# RcMPPT-Debug.net
KiCad netlist of a schematic drawn in Altium Designer
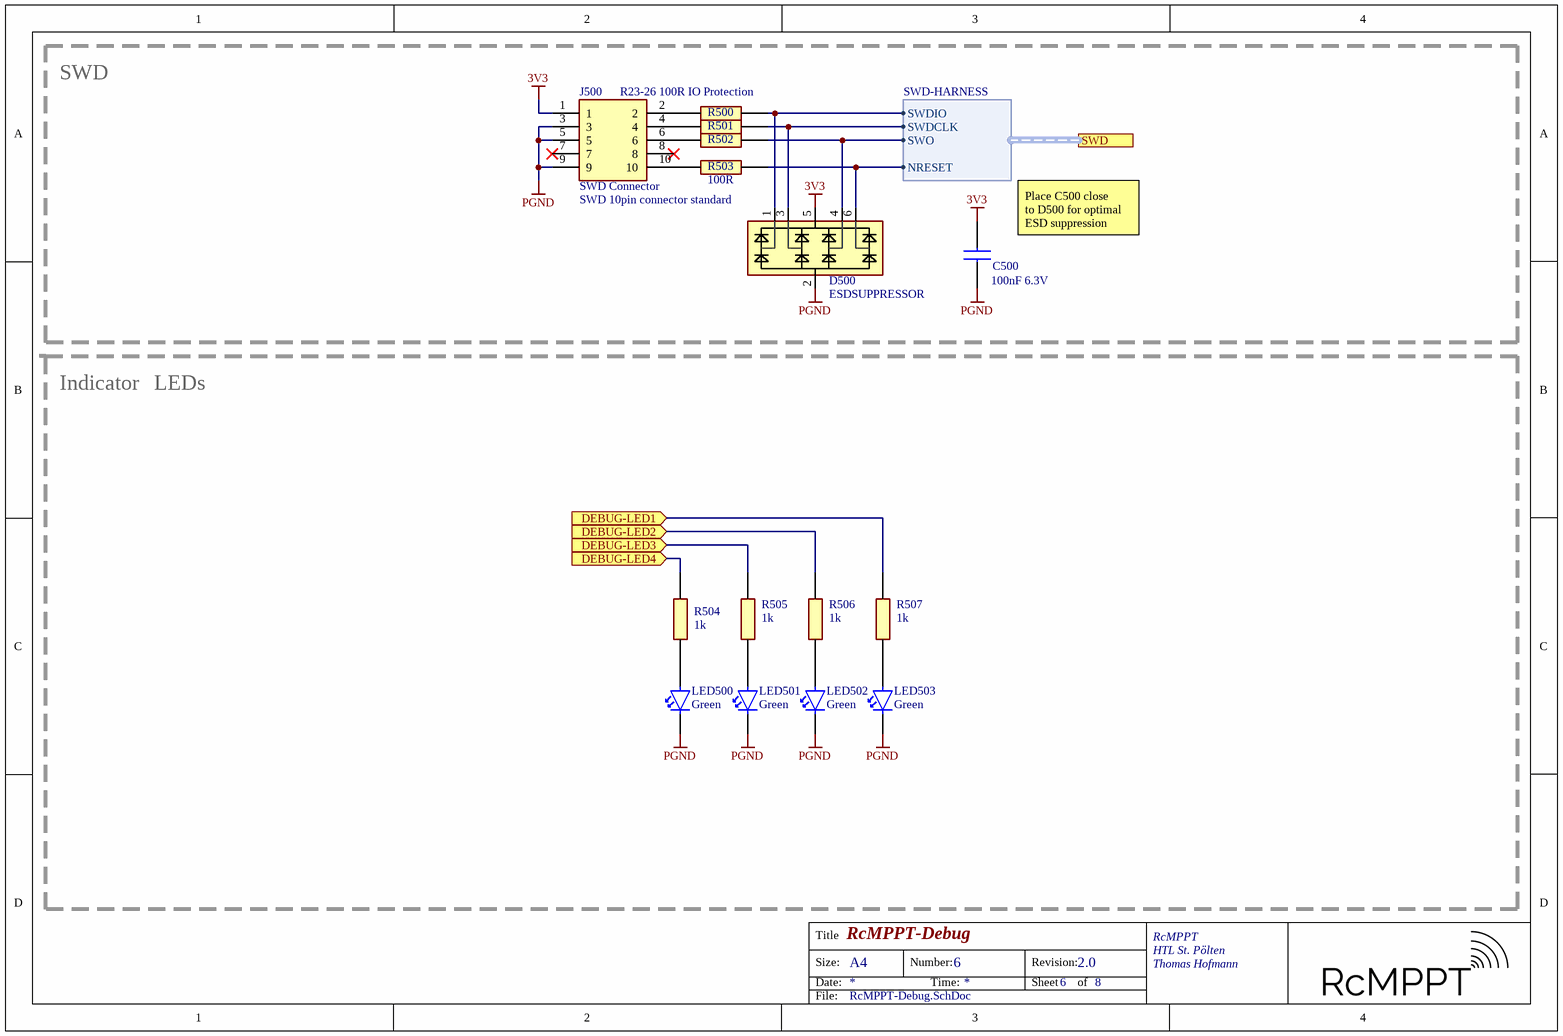
[diagram p0: RcMPPT-Debug.SchDoc]

(export (version "E")
  (design (tool "Eeschema 10.0.6"))
  (components
    (comp (ref "C500")
      (value "100nF 6.3V")
      (footprint "CAPC1608X97N")
      (description "Capacitor")
      (libsource (lib "RcMPPTLib") (part "C0603"))
    )
    (comp (ref "D500")
      (value "ESDSUPPRESSOR")
      (footprint "SOT23-6")
      (description "TVS Diode Array")
      (libsource (lib "RcMPPTLib") (part "ESDSUPPRESSOR"))
    )
    (comp (ref "J500")
      (value "SWD Connector")
      (footprint "HUSSP10W40P127_2X5_635X340X420P")
      (description "Connector")
      (fields
        (field (name "MANUFACTURER_PART_NUMBER") "M50-3600542R")
        (field (name "MOUSER PART NUMBER") "855-M50-3600542R")
      )
      (libsource (lib "RcMPPTLib") (part "M50-3600542R"))
    )
    (comp (ref "LED500")
      (value "Green")
      (footprint "CHIPLED_0603")
      (description "LED")
      (libsource (lib "RcMPPTLib") (part "CHIPLED0603"))
    )
    (comp (ref "LED501")
      (value "Green")
      (footprint "CHIPLED_0603")
      (description "LED")
      (libsource (lib "RcMPPTLib") (part "CHIPLED0603"))
    )
    (comp (ref "LED502")
      (value "Green")
      (footprint "CHIPLED_0603")
      (description "LED")
      (libsource (lib "RcMPPTLib") (part "CHIPLED0603"))
    )
    (comp (ref "LED503")
      (value "Green")
      (footprint "CHIPLED_0603")
      (description "LED")
      (libsource (lib "RcMPPTLib") (part "CHIPLED0603"))
    )
    (comp (ref "R500")
      (value "100R")
      (footprint "RESC1005X40N")
      (description "Resistor")
      (libsource (lib "RcMPPTLib") (part "R0402"))
    )
    (comp (ref "R501")
      (value "100R")
      (footprint "RESC1005X40N")
      (description "Resistor")
      (libsource (lib "RcMPPTLib") (part "R0402"))
    )
    (comp (ref "R502")
      (value "100R")
      (footprint "RESC1005X40N")
      (description "Resistor")
      (libsource (lib "RcMPPTLib") (part "R0402"))
    )
    (comp (ref "R503")
      (value "100R")
      (footprint "RESC1005X40N")
      (description "Resistor")
      (libsource (lib "RcMPPTLib") (part "R0402"))
    )
    (comp (ref "R504")
      (value "1k")
      (footprint "RESC1608X50N")
      (description "Resistor")
      (libsource (lib "RcMPPTLib") (part "R0603"))
    )
    (comp (ref "R505")
      (value "1k")
      (footprint "RESC1608X50N")
      (description "Resistor")
      (libsource (lib "RcMPPTLib") (part "R0603"))
    )
    (comp (ref "R506")
      (value "1k")
      (footprint "RESC1608X50N")
      (description "Resistor")
      (libsource (lib "RcMPPTLib") (part "R0603"))
    )
    (comp (ref "R507")
      (value "1k")
      (footprint "RESC1608X50N")
      (description "Resistor")
      (libsource (lib "RcMPPTLib") (part "R0603"))
    )
  )
  (nets
    (net (code "2") (name "/DEBUG-LED1") (class "Default")
      (node (ref "R507") (pin "1") (pinfunction "1_1") (pintype "passive"))
    )
    (net (code "3") (name "/DEBUG-LED2") (class "Default")
      (node (ref "R506") (pin "1") (pinfunction "1_1") (pintype "passive"))
    )
    (net (code "4") (name "/DEBUG-LED3") (class "Default")
      (node (ref "R505") (pin "1") (pinfunction "1_1") (pintype "passive"))
    )
    (net (code "5") (name "/DEBUG-LED4") (class "Default")
      (node (ref "R504") (pin "1") (pinfunction "1_1") (pintype "passive"))
    )
    (net (code "7") (name "3V3") (class "Default")
      (node (ref "C500") (pin "2") (pinfunction "2_2") (pintype "passive"))
      (node (ref "D500") (pin "5") (pinfunction "VDD_5") (pintype "passive"))
      (node (ref "J500") (pin "1") (pinfunction "1_1") (pintype "passive"))
    )
    (net (code "8") (name "Net-(D500-CH1)") (class "Default")
      (node (ref "D500") (pin "1") (pinfunction "CH1_1") (pintype "passive"))
      (node (ref "R500") (pin "2") (pinfunction "2_2") (pintype "passive"))
    )
    (net (code "9") (name "Net-(D500-CH2)") (class "Default")
      (node (ref "D500") (pin "3") (pinfunction "CH2_3") (pintype "passive"))
      (node (ref "R501") (pin "2") (pinfunction "2_2") (pintype "passive"))
    )
    (net (code "10") (name "Net-(D500-CH3)") (class "Default")
      (node (ref "D500") (pin "4") (pinfunction "CH3_4") (pintype "passive"))
      (node (ref "R502") (pin "2") (pinfunction "2_2") (pintype "passive"))
    )
    (net (code "11") (name "Net-(D500-CH4)") (class "Default")
      (node (ref "D500") (pin "6") (pinfunction "CH4_6") (pintype "passive"))
      (node (ref "R503") (pin "2") (pinfunction "2_2") (pintype "passive"))
    )
    (net (code "12") (name "Net-(J500-Pad2)") (class "Default")
      (node (ref "J500") (pin "2") (pinfunction "2_2") (pintype "passive"))
      (node (ref "R500") (pin "1") (pinfunction "1_1") (pintype "passive"))
    )
    (net (code "13") (name "Net-(J500-Pad4)") (class "Default")
      (node (ref "J500") (pin "4") (pinfunction "4_4") (pintype "passive"))
      (node (ref "R501") (pin "1") (pinfunction "1_1") (pintype "passive"))
    )
    (net (code "14") (name "Net-(J500-Pad6)") (class "Default")
      (node (ref "J500") (pin "6") (pinfunction "6_6") (pintype "passive"))
      (node (ref "R502") (pin "1") (pinfunction "1_1") (pintype "passive"))
    )
    (net (code "15") (name "Net-(J500-Pad10)") (class "Default")
      (node (ref "J500") (pin "10") (pinfunction "10_10") (pintype "passive"))
      (node (ref "R503") (pin "1") (pinfunction "1_1") (pintype "passive"))
    )
    (net (code "16") (name "Net-(LED500-A)") (class "Default")
      (node (ref "LED500") (pin "2") (pinfunction "A_2") (pintype "passive"))
      (node (ref "R504") (pin "2") (pinfunction "2_2") (pintype "passive"))
    )
    (net (code "17") (name "Net-(LED501-A)") (class "Default")
      (node (ref "LED501") (pin "2") (pinfunction "A_2") (pintype "passive"))
      (node (ref "R505") (pin "2") (pinfunction "2_2") (pintype "passive"))
    )
    (net (code "18") (name "Net-(LED502-A)") (class "Default")
      (node (ref "LED502") (pin "2") (pinfunction "A_2") (pintype "passive"))
      (node (ref "R506") (pin "2") (pinfunction "2_2") (pintype "passive"))
    )
    (net (code "19") (name "Net-(LED503-A)") (class "Default")
      (node (ref "LED503") (pin "2") (pinfunction "A_2") (pintype "passive"))
      (node (ref "R507") (pin "2") (pinfunction "2_2") (pintype "passive"))
    )
    (net (code "20") (name "PGND") (class "Default")
      (node (ref "C500") (pin "1") (pinfunction "1_1") (pintype "passive"))
      (node (ref "D500") (pin "2") (pinfunction "GND_2") (pintype "passive"))
      (node (ref "J500") (pin "3") (pinfunction "3_3") (pintype "passive"))
      (node (ref "J500") (pin "5") (pinfunction "5_5") (pintype "passive"))
      (node (ref "J500") (pin "9") (pinfunction "9_9") (pintype "passive"))
      (node (ref "LED500") (pin "1") (pinfunction "K_1") (pintype "passive"))
      (node (ref "LED501") (pin "1") (pinfunction "K_1") (pintype "passive"))
      (node (ref "LED502") (pin "1") (pinfunction "K_1") (pintype "passive"))
      (node (ref "LED503") (pin "1") (pinfunction "K_1") (pintype "passive"))
    )
    (net (code "21") (name "unconnected-(J500-Pad7)") (class "Default")
      (node (ref "J500") (pin "7") (pinfunction "7_7") (pintype "passive+no_connect"))
    )
    (net (code "22") (name "unconnected-(J500-Pad8)") (class "Default")
      (node (ref "J500") (pin "8") (pinfunction "8_8") (pintype "passive+no_connect"))
    )
  )
)
